# top.net
KiCad netlist of a schematic drawn in Altium Designer
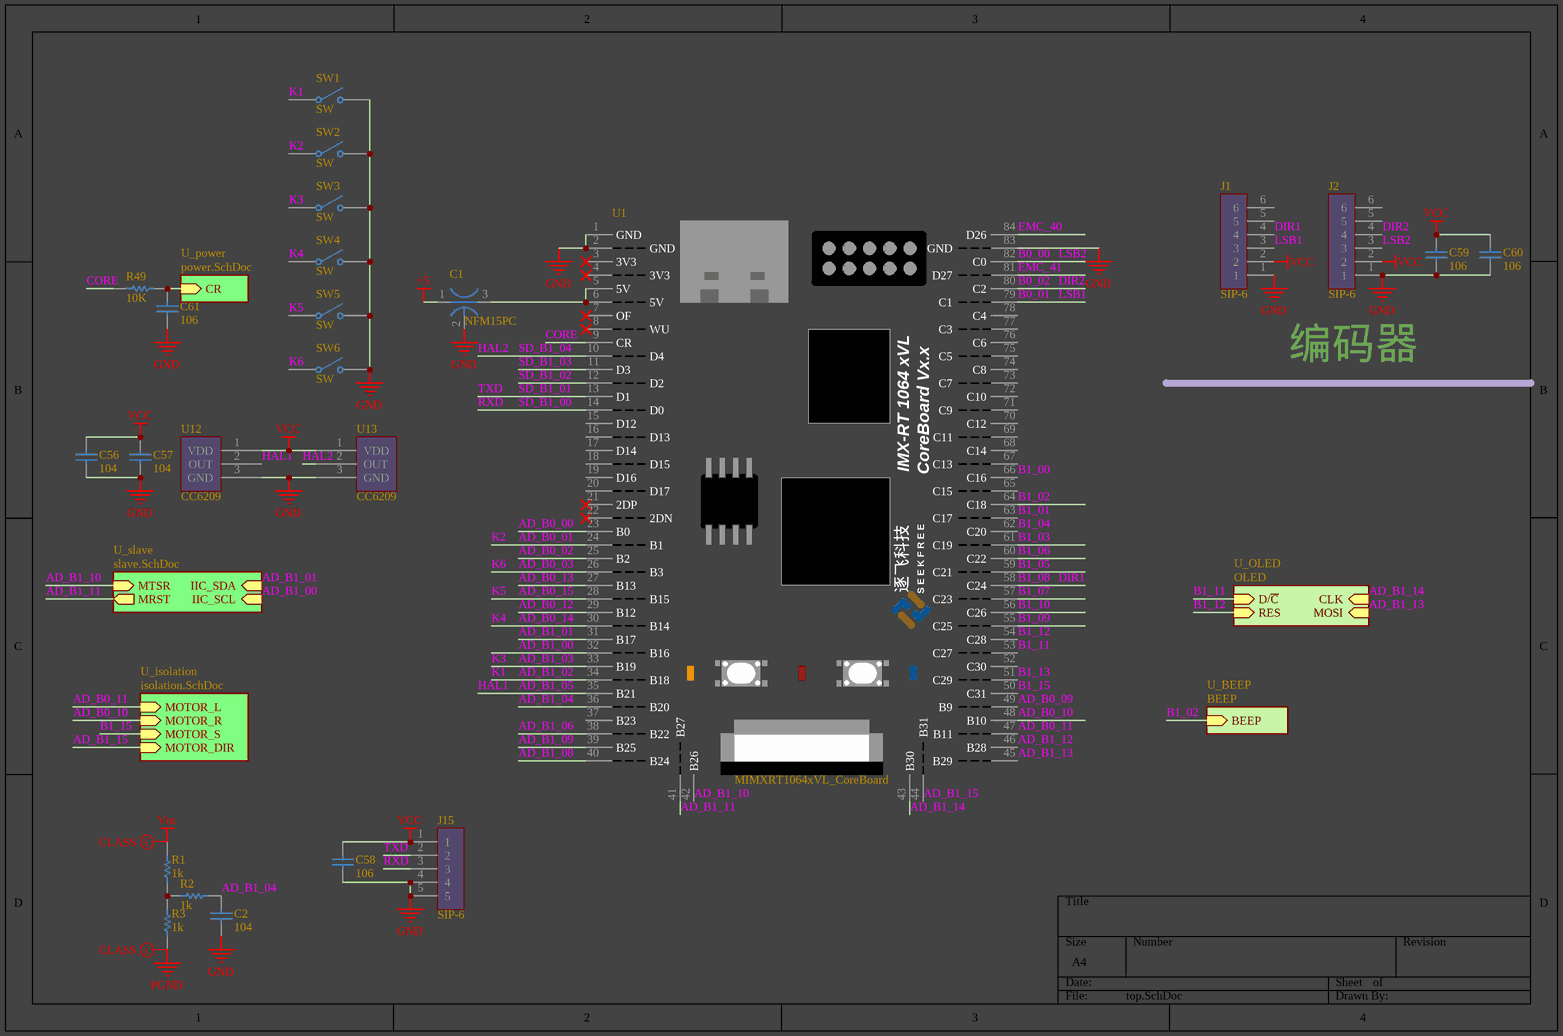
[diagram p0: top.SchDoc]

(export (version "E")
  (design (tool "Eeschema 10.0.6"))
  (components
    (comp (ref "C1")
      (value "NFM15PC")
      (footprint "FILTER-SMD_3P-L1.0-W0.5-L")
      (fields
        (field (name "BOM_SUPPLIER PART") "C162672")
        (field (name "BOM_MANUFACTURER PART") "NFM15PC473C1C3D")
        (field (name "CONTRIBUTOR") "LCSC")
      )
      (libsource (lib "iMag") (part "陶瓷滤波器"))
    )
    (comp (ref "C2")
      (value "104")
      (footprint "C0603")
      (description "Capacitor")
      (fields (field (name "PUBLISHER") "Altium Limited"))
      (libsource (lib "iMag") (part "电容"))
    )
    (comp (ref "C56")
      (value "104")
      (footprint "C0603")
      (description "Capacitor")
      (fields (field (name "PUBLISHER") "Altium Limited"))
      (libsource (lib "iMag") (part "电容"))
    )
    (comp (ref "C57")
      (value "104")
      (footprint "C0603")
      (description "Capacitor")
      (fields (field (name "PUBLISHER") "Altium Limited"))
      (libsource (lib "iMag") (part "电容"))
    )
    (comp (ref "C58")
      (value "106")
      (footprint "C0603")
      (description "Capacitor")
      (fields (field (name "PUBLISHER") "Altium Limited"))
      (libsource (lib "iMag") (part "电容"))
    )
    (comp (ref "C59")
      (value "106")
      (footprint "C0603")
      (description "Capacitor")
      (fields (field (name "PUBLISHER") "Altium Limited"))
      (libsource (lib "iMag") (part "电容"))
    )
    (comp (ref "C60")
      (value "106")
      (footprint "C0603")
      (description "Capacitor")
      (fields (field (name "PUBLISHER") "Altium Limited"))
      (libsource (lib "iMag") (part "电容"))
    )
    (comp (ref "C61")
      (value "106")
      (footprint "C0603")
      (description "Capacitor")
      (fields (field (name "PUBLISHER") "Altium Limited"))
      (libsource (lib "iMag") (part "电容"))
    )
    (comp (ref "J1") (value "SIP-6") (footprint "2.54简易牛角座6P") (libsource (lib "iMag") (part "SIP-6")))
    (comp (ref "J2") (value "SIP-6") (footprint "2.54简易牛角座6P") (libsource (lib "iMag") (part "SIP-6")))
    (comp (ref "J15") (value "SIP-6") (footprint "2.54排针1X5") (libsource (lib "iMag") (part "SIP-5")))
    (comp (ref "R1")
      (value "1k")
      (footprint "R0603")
      (description "Resistor")
      (fields (field (name "PUBLISHER") "Altium Limited"))
      (libsource (lib "iMag") (part "电阻"))
    )
    (comp (ref "R2")
      (value "1k")
      (footprint "R0603")
      (description "Resistor")
      (fields (field (name "PUBLISHER") "Altium Limited"))
      (libsource (lib "iMag") (part "电阻"))
    )
    (comp (ref "R3")
      (value "1k")
      (footprint "R0603")
      (description "Resistor")
      (fields (field (name "PUBLISHER") "Altium Limited"))
      (libsource (lib "iMag") (part "电阻"))
    )
    (comp (ref "R49")
      (value "10K")
      (footprint "R0603")
      (description "Resistor")
      (fields (field (name "PUBLISHER") "Altium Limited"))
      (libsource (lib "iMag") (part "电阻"))
    )
    (comp (ref "SW1")
      (value "SW")
      (footprint "KEY-SMD_4P-L4.2-W3.2-P2.20-LS4.6")
      (description "Single-Pole, Single-Throw Switch")
      (libsource (lib "iMag") (part "Switch"))
    )
    (comp (ref "SW2")
      (value "SW")
      (footprint "KEY-SMD_4P-L4.2-W3.2-P2.20-LS4.6")
      (description "Single-Pole, Single-Throw Switch")
      (libsource (lib "iMag") (part "Switch"))
    )
    (comp (ref "SW3")
      (value "SW")
      (footprint "KEY-SMD_4P-L4.2-W3.2-P2.20-LS4.6")
      (description "Single-Pole, Single-Throw Switch")
      (libsource (lib "iMag") (part "Switch"))
    )
    (comp (ref "SW4")
      (value "SW")
      (footprint "KEY-SMD_4P-L4.2-W3.2-P2.20-LS4.6")
      (description "Single-Pole, Single-Throw Switch")
      (libsource (lib "iMag") (part "Switch"))
    )
    (comp (ref "SW5")
      (value "SW")
      (footprint "KEY-SMD_4P-L4.2-W3.2-P2.20-LS4.6")
      (description "Single-Pole, Single-Throw Switch")
      (libsource (lib "iMag") (part "Switch"))
    )
    (comp (ref "SW6")
      (value "SW")
      (footprint "KEY-SMD_4P-L4.2-W3.2-P2.20-LS4.6")
      (description "Single-Pole, Single-Throw Switch")
      (libsource (lib "iMag") (part "Switch"))
    )
    (comp (ref "U1")
      (value "MIMXRT1064xVL_CoreBoard")
      (footprint "MIMXRT1064xVL_CoreBoard")
      (description "逐飞科技i.MX RT1064核心板整体原理，可直接使用")
      (libsource (lib "iMag") (part "MIMXRT1064xVL_CoreBoard"))
    )
    (comp (ref "U12") (value "CC6209") (footprint "SOT-23") (libsource (lib "") (part "霍尔开关_1")))
    (comp (ref "U13") (value "CC6209") (footprint "SOT-23") (libsource (lib "iMag") (part "霍尔开关")))
  )
  (nets
    (net (code "1") (name "+5") (class "Default")
      (node (ref "C1") (pin "1") (pinfunction "IN_1") (pintype "passive"))
    )
    (net (code "2") (name "/AD_B0_00") (class "Default")
      (node (ref "U1") (pin "23") (pinfunction "B0_23") (pintype "passive"))
    )
    (net (code "3") (name "/AD_B0_01") (class "Default")
      (node (ref "SW2") (pin "1") (pinfunction "COMMON_1") (pintype "passive"))
      (node (ref "U1") (pin "24") (pinfunction "B1_24") (pintype "passive"))
    )
    (net (code "4") (name "/AD_B0_02") (class "Default")
      (node (ref "U1") (pin "25") (pinfunction "B2_25") (pintype "passive"))
    )
    (net (code "5") (name "/AD_B0_03") (class "Default")
      (node (ref "SW6") (pin "1") (pinfunction "COMMON_1") (pintype "passive"))
      (node (ref "U1") (pin "26") (pinfunction "B3_26") (pintype "passive"))
    )
    (net (code "6") (name "/AD_B0_09") (class "Default")
      (node (ref "U1") (pin "49") (pinfunction "B9_49") (pintype "passive"))
    )
    (net (code "7") (name "/AD_B0_10") (class "Default")
      (node (ref "U1") (pin "48") (pinfunction "B10_48") (pintype "passive"))
    )
    (net (code "8") (name "/AD_B0_11") (class "Default")
      (node (ref "U1") (pin "47") (pinfunction "B11_47") (pintype "passive"))
    )
    (net (code "9") (name "/AD_B0_12") (class "Default")
      (node (ref "U1") (pin "29") (pinfunction "B12_29") (pintype "passive"))
    )
    (net (code "10") (name "/AD_B0_13") (class "Default")
      (node (ref "U1") (pin "27") (pinfunction "B13_27") (pintype "passive"))
    )
    (net (code "11") (name "/AD_B0_14") (class "Default")
      (node (ref "SW4") (pin "1") (pinfunction "COMMON_1") (pintype "passive"))
      (node (ref "U1") (pin "30") (pinfunction "B14_30") (pintype "passive"))
    )
    (net (code "12") (name "/AD_B0_15") (class "Default")
      (node (ref "SW5") (pin "1") (pinfunction "COMMON_1") (pintype "passive"))
      (node (ref "U1") (pin "28") (pinfunction "B15_28") (pintype "passive"))
    )
    (net (code "13") (name "/AD_B1_00") (class "Default")
      (node (ref "U1") (pin "32") (pinfunction "B16_32") (pintype "passive"))
    )
    (net (code "14") (name "/AD_B1_01") (class "Default")
      (node (ref "U1") (pin "31") (pinfunction "B17_31") (pintype "passive"))
    )
    (net (code "15") (name "/AD_B1_02") (class "Default")
      (node (ref "SW1") (pin "1") (pinfunction "COMMON_1") (pintype "passive"))
      (node (ref "U1") (pin "34") (pinfunction "B18_34") (pintype "passive"))
    )
    (net (code "16") (name "/AD_B1_03") (class "Default")
      (node (ref "SW3") (pin "1") (pinfunction "COMMON_1") (pintype "passive"))
      (node (ref "U1") (pin "33") (pinfunction "B19_33") (pintype "passive"))
    )
    (net (code "17") (name "/AD_B1_04") (class "Default")
      (node (ref "C2") (pin "2") (pinfunction "2_2") (pintype "passive"))
      (node (ref "R2") (pin "1") (pinfunction "1_1") (pintype "passive"))
      (node (ref "U1") (pin "36") (pinfunction "B20_36") (pintype "passive"))
    )
    (net (code "18") (name "/AD_B1_05") (class "Default")
      (node (ref "U1") (pin "35") (pinfunction "B21_35") (pintype "passive"))
      (node (ref "U12") (pin "2") (pinfunction "OUT_2") (pintype "passive"))
    )
    (net (code "19") (name "/AD_B1_06") (class "Default")
      (node (ref "U1") (pin "38") (pinfunction "B22_38") (pintype "passive"))
    )
    (net (code "20") (name "/AD_B1_08") (class "Default")
      (node (ref "U1") (pin "40") (pinfunction "B24_40") (pintype "passive"))
    )
    (net (code "21") (name "/AD_B1_09") (class "Default")
      (node (ref "U1") (pin "39") (pinfunction "B25_39") (pintype "passive"))
    )
    (net (code "22") (name "/AD_B1_10") (class "Default")
      (node (ref "U1") (pin "42") (pinfunction "B26_42") (pintype "passive"))
    )
    (net (code "23") (name "/AD_B1_11") (class "Default")
      (node (ref "U1") (pin "41") (pinfunction "B27_41") (pintype "passive"))
    )
    (net (code "24") (name "/AD_B1_12") (class "Default")
      (node (ref "U1") (pin "46") (pinfunction "B28_46") (pintype "passive"))
    )
    (net (code "25") (name "/AD_B1_13") (class "Default")
      (node (ref "U1") (pin "45") (pinfunction "B29_45") (pintype "passive"))
    )
    (net (code "26") (name "/AD_B1_14") (class "Default")
      (node (ref "U1") (pin "43") (pinfunction "B30_43") (pintype "passive"))
    )
    (net (code "27") (name "/AD_B1_15") (class "Default")
      (node (ref "U1") (pin "44") (pinfunction "B31_44") (pintype "passive"))
    )
    (net (code "28") (name "/B0_00") (class "Default")
      (node (ref "J2") (pin "3") (pinfunction "3_3") (pintype "passive"))
      (node (ref "U1") (pin "82") (pinfunction "C0_82") (pintype "passive"))
    )
    (net (code "29") (name "/B0_01") (class "Default")
      (node (ref "J1") (pin "3") (pinfunction "3_3") (pintype "passive"))
      (node (ref "U1") (pin "79") (pinfunction "C1_79") (pintype "passive"))
    )
    (net (code "30") (name "/B0_02") (class "Default")
      (node (ref "J2") (pin "4") (pinfunction "4_4") (pintype "passive"))
      (node (ref "U1") (pin "80") (pinfunction "C2_80") (pintype "passive"))
    )
    (net (code "31") (name "/B1_00") (class "Default")
      (node (ref "U1") (pin "66") (pinfunction "C16_66") (pintype "passive"))
    )
    (net (code "32") (name "/B1_01") (class "Default")
      (node (ref "U1") (pin "63") (pinfunction "C17_63") (pintype "passive"))
    )
    (net (code "33") (name "/B1_02") (class "Default")
      (node (ref "U1") (pin "64") (pinfunction "C18_64") (pintype "passive"))
    )
    (net (code "34") (name "/B1_03") (class "Default")
      (node (ref "U1") (pin "61") (pinfunction "C19_61") (pintype "passive"))
    )
    (net (code "35") (name "/B1_04") (class "Default")
      (node (ref "U1") (pin "62") (pinfunction "C20_62") (pintype "passive"))
    )
    (net (code "36") (name "/B1_05") (class "Default")
      (node (ref "U1") (pin "59") (pinfunction "C21_59") (pintype "passive"))
    )
    (net (code "37") (name "/B1_06") (class "Default")
      (node (ref "U1") (pin "60") (pinfunction "C22_60") (pintype "passive"))
    )
    (net (code "38") (name "/B1_07") (class "Default")
      (node (ref "U1") (pin "57") (pinfunction "C23_57") (pintype "passive"))
    )
    (net (code "39") (name "/B1_08") (class "Default")
      (node (ref "J1") (pin "4") (pinfunction "4_4") (pintype "passive"))
      (node (ref "U1") (pin "58") (pinfunction "C24_58") (pintype "passive"))
    )
    (net (code "40") (name "/B1_09") (class "Default")
      (node (ref "U1") (pin "55") (pinfunction "C25_55") (pintype "passive"))
    )
    (net (code "41") (name "/B1_10") (class "Default")
      (node (ref "U1") (pin "56") (pinfunction "C26_56") (pintype "passive"))
    )
    (net (code "42") (name "/B1_11") (class "Default")
      (node (ref "U1") (pin "53") (pinfunction "C27_53") (pintype "passive"))
    )
    (net (code "43") (name "/B1_12") (class "Default")
      (node (ref "U1") (pin "54") (pinfunction "C28_54") (pintype "passive"))
    )
    (net (code "44") (name "/B1_13") (class "Default")
      (node (ref "U1") (pin "51") (pinfunction "C29_51") (pintype "passive"))
    )
    (net (code "45") (name "/B1_15") (class "Default")
      (node (ref "U1") (pin "50") (pinfunction "C31_50") (pintype "passive"))
    )
    (net (code "46") (name "/CORE") (class "Default")
      (node (ref "R49") (pin "2") (pinfunction "2_2") (pintype "passive"))
      (node (ref "U1") (pin "9") (pinfunction "CR_9") (pintype "passive"))
    )
    (net (code "47") (name "/CR") (class "Default")
      (node (ref "C61") (pin "2") (pinfunction "2_2") (pintype "passive"))
      (node (ref "R49") (pin "1") (pinfunction "1_1") (pintype "passive"))
    )
    (net (code "48") (name "/EMC_40") (class "Default")
      (node (ref "U1") (pin "84") (pinfunction "D26_84") (pintype "passive"))
    )
    (net (code "49") (name "/EMC_41") (class "Default")
      (node (ref "U1") (pin "81") (pinfunction "D27_81") (pintype "passive"))
    )
    (net (code "50") (name "/HAL2") (class "Default")
      (node (ref "U1") (pin "10") (pinfunction "D4_10") (pintype "passive"))
      (node (ref "U13") (pin "2") (pinfunction "OUT_2") (pintype "passive"))
    )
    (net (code "51") (name "/RXD") (class "Default")
      (node (ref "J15") (pin "3") (pinfunction "3_3") (pintype "passive"))
      (node (ref "U1") (pin "14") (pinfunction "D0_14") (pintype "passive"))
    )
    (net (code "52") (name "/SD_B1_01") (class "Default")
      (node (ref "J15") (pin "2") (pinfunction "2_2") (pintype "passive"))
      (node (ref "U1") (pin "13") (pinfunction "D1_13") (pintype "passive"))
    )
    (net (code "53") (name "/SD_B1_02") (class "Default")
      (node (ref "U1") (pin "12") (pinfunction "D2_12") (pintype "passive"))
    )
    (net (code "54") (name "/SD_B1_03") (class "Default")
      (node (ref "U1") (pin "11") (pinfunction "D3_11") (pintype "passive"))
    )
    (net (code "55") (name "GND") (class "Default")
      (node (ref "C1") (pin "2") (pinfunction "GND_2") (pintype "passive"))
      (node (ref "C2") (pin "1") (pinfunction "1_1") (pintype "passive"))
      (node (ref "C56") (pin "1") (pinfunction "1_1") (pintype "passive"))
      (node (ref "C57") (pin "1") (pinfunction "1_1") (pintype "passive"))
      (node (ref "C58") (pin "1") (pinfunction "1_1") (pintype "passive"))
      (node (ref "C59") (pin "1") (pinfunction "1_1") (pintype "passive"))
      (node (ref "C60") (pin "1") (pinfunction "1_1") (pintype "passive"))
      (node (ref "C61") (pin "1") (pinfunction "1_1") (pintype "passive"))
      (node (ref "J1") (pin "1") (pinfunction "1_1") (pintype "passive"))
      (node (ref "J15") (pin "4") (pinfunction "4_4") (pintype "passive"))
      (node (ref "J15") (pin "5") (pinfunction "5_5") (pintype "passive"))
      (node (ref "J2") (pin "1") (pinfunction "1_1") (pintype "passive"))
      (node (ref "SW1") (pin "2") (pinfunction "NO_2") (pintype "passive"))
      (node (ref "SW2") (pin "2") (pinfunction "NO_2") (pintype "passive"))
      (node (ref "SW3") (pin "2") (pinfunction "NO_2") (pintype "passive"))
      (node (ref "SW4") (pin "2") (pinfunction "NO_2") (pintype "passive"))
      (node (ref "SW5") (pin "2") (pinfunction "NO_2") (pintype "passive"))
      (node (ref "SW6") (pin "2") (pinfunction "NO_2") (pintype "passive"))
      (node (ref "U1") (pin "1") (pinfunction "GND_1") (pintype "passive"))
      (node (ref "U1") (pin "2") (pinfunction "GND_2") (pintype "passive"))
      (node (ref "U1") (pin "83") (pinfunction "GND_83") (pintype "passive"))
      (node (ref "U12") (pin "3") (pinfunction "GND_3") (pintype "passive"))
      (node (ref "U13") (pin "3") (pinfunction "GND_3") (pintype "passive"))
    )
    (net (code "56") (name "Net-(C1-OUT)") (class "Default")
      (node (ref "C1") (pin "3") (pinfunction "OUT_3") (pintype "passive"))
      (node (ref "U1") (pin "5") (pinfunction "5V_5") (pintype "passive"))
      (node (ref "U1") (pin "6") (pinfunction "5V_6") (pintype "passive"))
    )
    (net (code "57") (name "Net-(R1-Pad1)") (class "Default")
      (node (ref "R1") (pin "1") (pinfunction "1_1") (pintype "passive"))
      (node (ref "R2") (pin "2") (pinfunction "2_2") (pintype "passive"))
      (node (ref "R3") (pin "2") (pinfunction "2_2") (pintype "passive"))
    )
    (net (code "58") (name "PGND") (class "Default")
      (node (ref "R3") (pin "1") (pinfunction "1_1") (pintype "passive"))
    )
    (net (code "59") (name "VCC") (class "Default")
      (node (ref "C56") (pin "2") (pinfunction "2_2") (pintype "passive"))
      (node (ref "C57") (pin "2") (pinfunction "2_2") (pintype "passive"))
      (node (ref "C58") (pin "2") (pinfunction "2_2") (pintype "passive"))
      (node (ref "C59") (pin "2") (pinfunction "2_2") (pintype "passive"))
      (node (ref "C60") (pin "2") (pinfunction "2_2") (pintype "passive"))
      (node (ref "J1") (pin "2") (pinfunction "2_2") (pintype "passive"))
      (node (ref "J15") (pin "1") (pinfunction "1_1") (pintype "passive"))
      (node (ref "J2") (pin "2") (pinfunction "2_2") (pintype "passive"))
      (node (ref "U12") (pin "1") (pinfunction "VDD_1") (pintype "passive"))
      (node (ref "U13") (pin "1") (pinfunction "VDD_1") (pintype "passive"))
    )
    (net (code "60") (name "Vm") (class "Default")
      (node (ref "R1") (pin "2") (pinfunction "2_2") (pintype "passive"))
    )
    (net (code "61") (name "unconnected-(J1-Pad5)") (class "Default")
      (node (ref "J1") (pin "5") (pinfunction "5_5") (pintype "passive"))
    )
    (net (code "62") (name "unconnected-(J1-Pad6)") (class "Default")
      (node (ref "J1") (pin "6") (pinfunction "6_6") (pintype "passive"))
    )
    (net (code "63") (name "unconnected-(J2-Pad5)") (class "Default")
      (node (ref "J2") (pin "5") (pinfunction "5_5") (pintype "passive"))
    )
    (net (code "64") (name "unconnected-(J2-Pad6)") (class "Default")
      (node (ref "J2") (pin "6") (pinfunction "6_6") (pintype "passive"))
    )
    (net (code "65") (name "unconnected-(U1-2DN-Pad22)") (class "Default")
      (node (ref "U1") (pin "22") (pinfunction "2DN_22") (pintype "passive+no_connect"))
    )
    (net (code "66") (name "unconnected-(U1-2DP-Pad21)") (class "Default")
      (node (ref "U1") (pin "21") (pinfunction "2DP_21") (pintype "passive+no_connect"))
    )
    (net (code "67") (name "unconnected-(U1-3V3-Pad3)") (class "Default")
      (node (ref "U1") (pin "3") (pinfunction "3V3_3") (pintype "passive+no_connect"))
    )
    (net (code "68") (name "unconnected-(U1-3V3-Pad4)") (class "Default")
      (node (ref "U1") (pin "4") (pinfunction "3V3_4") (pintype "passive+no_connect"))
    )
    (net (code "69") (name "unconnected-(U1-B23-Pad37)") (class "Default")
      (node (ref "U1") (pin "37") (pinfunction "B23_37") (pintype "passive"))
    )
    (net (code "70") (name "unconnected-(U1-C3-Pad77)") (class "Default")
      (node (ref "U1") (pin "77") (pinfunction "C3_77") (pintype "passive"))
    )
    (net (code "71") (name "unconnected-(U1-C4-Pad78)") (class "Default")
      (node (ref "U1") (pin "78") (pinfunction "C4_78") (pintype "passive"))
    )
    (net (code "72") (name "unconnected-(U1-C5-Pad75)") (class "Default")
      (node (ref "U1") (pin "75") (pinfunction "C5_75") (pintype "passive"))
    )
    (net (code "73") (name "unconnected-(U1-C6-Pad76)") (class "Default")
      (node (ref "U1") (pin "76") (pinfunction "C6_76") (pintype "passive"))
    )
    (net (code "74") (name "unconnected-(U1-C7-Pad73)") (class "Default")
      (node (ref "U1") (pin "73") (pinfunction "C7_73") (pintype "passive"))
    )
    (net (code "75") (name "unconnected-(U1-C8-Pad74)") (class "Default")
      (node (ref "U1") (pin "74") (pinfunction "C8_74") (pintype "passive"))
    )
    (net (code "76") (name "unconnected-(U1-C9-Pad71)") (class "Default")
      (node (ref "U1") (pin "71") (pinfunction "C9_71") (pintype "passive"))
    )
    (net (code "77") (name "unconnected-(U1-C10-Pad72)") (class "Default")
      (node (ref "U1") (pin "72") (pinfunction "C10_72") (pintype "passive"))
    )
    (net (code "78") (name "unconnected-(U1-C11-Pad69)") (class "Default")
      (node (ref "U1") (pin "69") (pinfunction "C11_69") (pintype "passive"))
    )
    (net (code "79") (name "unconnected-(U1-C12-Pad70)") (class "Default")
      (node (ref "U1") (pin "70") (pinfunction "C12_70") (pintype "passive"))
    )
    (net (code "80") (name "unconnected-(U1-C13-Pad67)") (class "Default")
      (node (ref "U1") (pin "67") (pinfunction "C13_67") (pintype "passive"))
    )
    (net (code "81") (name "unconnected-(U1-C14-Pad68)") (class "Default")
      (node (ref "U1") (pin "68") (pinfunction "C14_68") (pintype "passive"))
    )
    (net (code "82") (name "unconnected-(U1-C15-Pad65)") (class "Default")
      (node (ref "U1") (pin "65") (pinfunction "C15_65") (pintype "passive"))
    )
    (net (code "83") (name "unconnected-(U1-C30-Pad52)") (class "Default")
      (node (ref "U1") (pin "52") (pinfunction "C30_52") (pintype "passive"))
    )
    (net (code "84") (name "unconnected-(U1-D12-Pad15)") (class "Default")
      (node (ref "U1") (pin "15") (pinfunction "D12_15") (pintype "passive"))
    )
    (net (code "85") (name "unconnected-(U1-D13-Pad16)") (class "Default")
      (node (ref "U1") (pin "16") (pinfunction "D13_16") (pintype "passive"))
    )
    (net (code "86") (name "unconnected-(U1-D14-Pad17)") (class "Default")
      (node (ref "U1") (pin "17") (pinfunction "D14_17") (pintype "passive"))
    )
    (net (code "87") (name "unconnected-(U1-D15-Pad18)") (class "Default")
      (node (ref "U1") (pin "18") (pinfunction "D15_18") (pintype "passive"))
    )
    (net (code "88") (name "unconnected-(U1-D16-Pad19)") (class "Default")
      (node (ref "U1") (pin "19") (pinfunction "D16_19") (pintype "passive"))
    )
    (net (code "89") (name "unconnected-(U1-D17-Pad20)") (class "Default")
      (node (ref "U1") (pin "20") (pinfunction "D17_20") (pintype "passive"))
    )
    (net (code "90") (name "unconnected-(U1-OF-Pad7)") (class "Default")
      (node (ref "U1") (pin "7") (pinfunction "OF_7") (pintype "passive+no_connect"))
    )
    (net (code "91") (name "unconnected-(U1-WU-Pad8)") (class "Default")
      (node (ref "U1") (pin "8") (pinfunction "WU_8") (pintype "passive+no_connect"))
    )
  )
)
